# NCU_PCB_Rev2.net
KiCad netlist of a schematic drawn in EAGLE
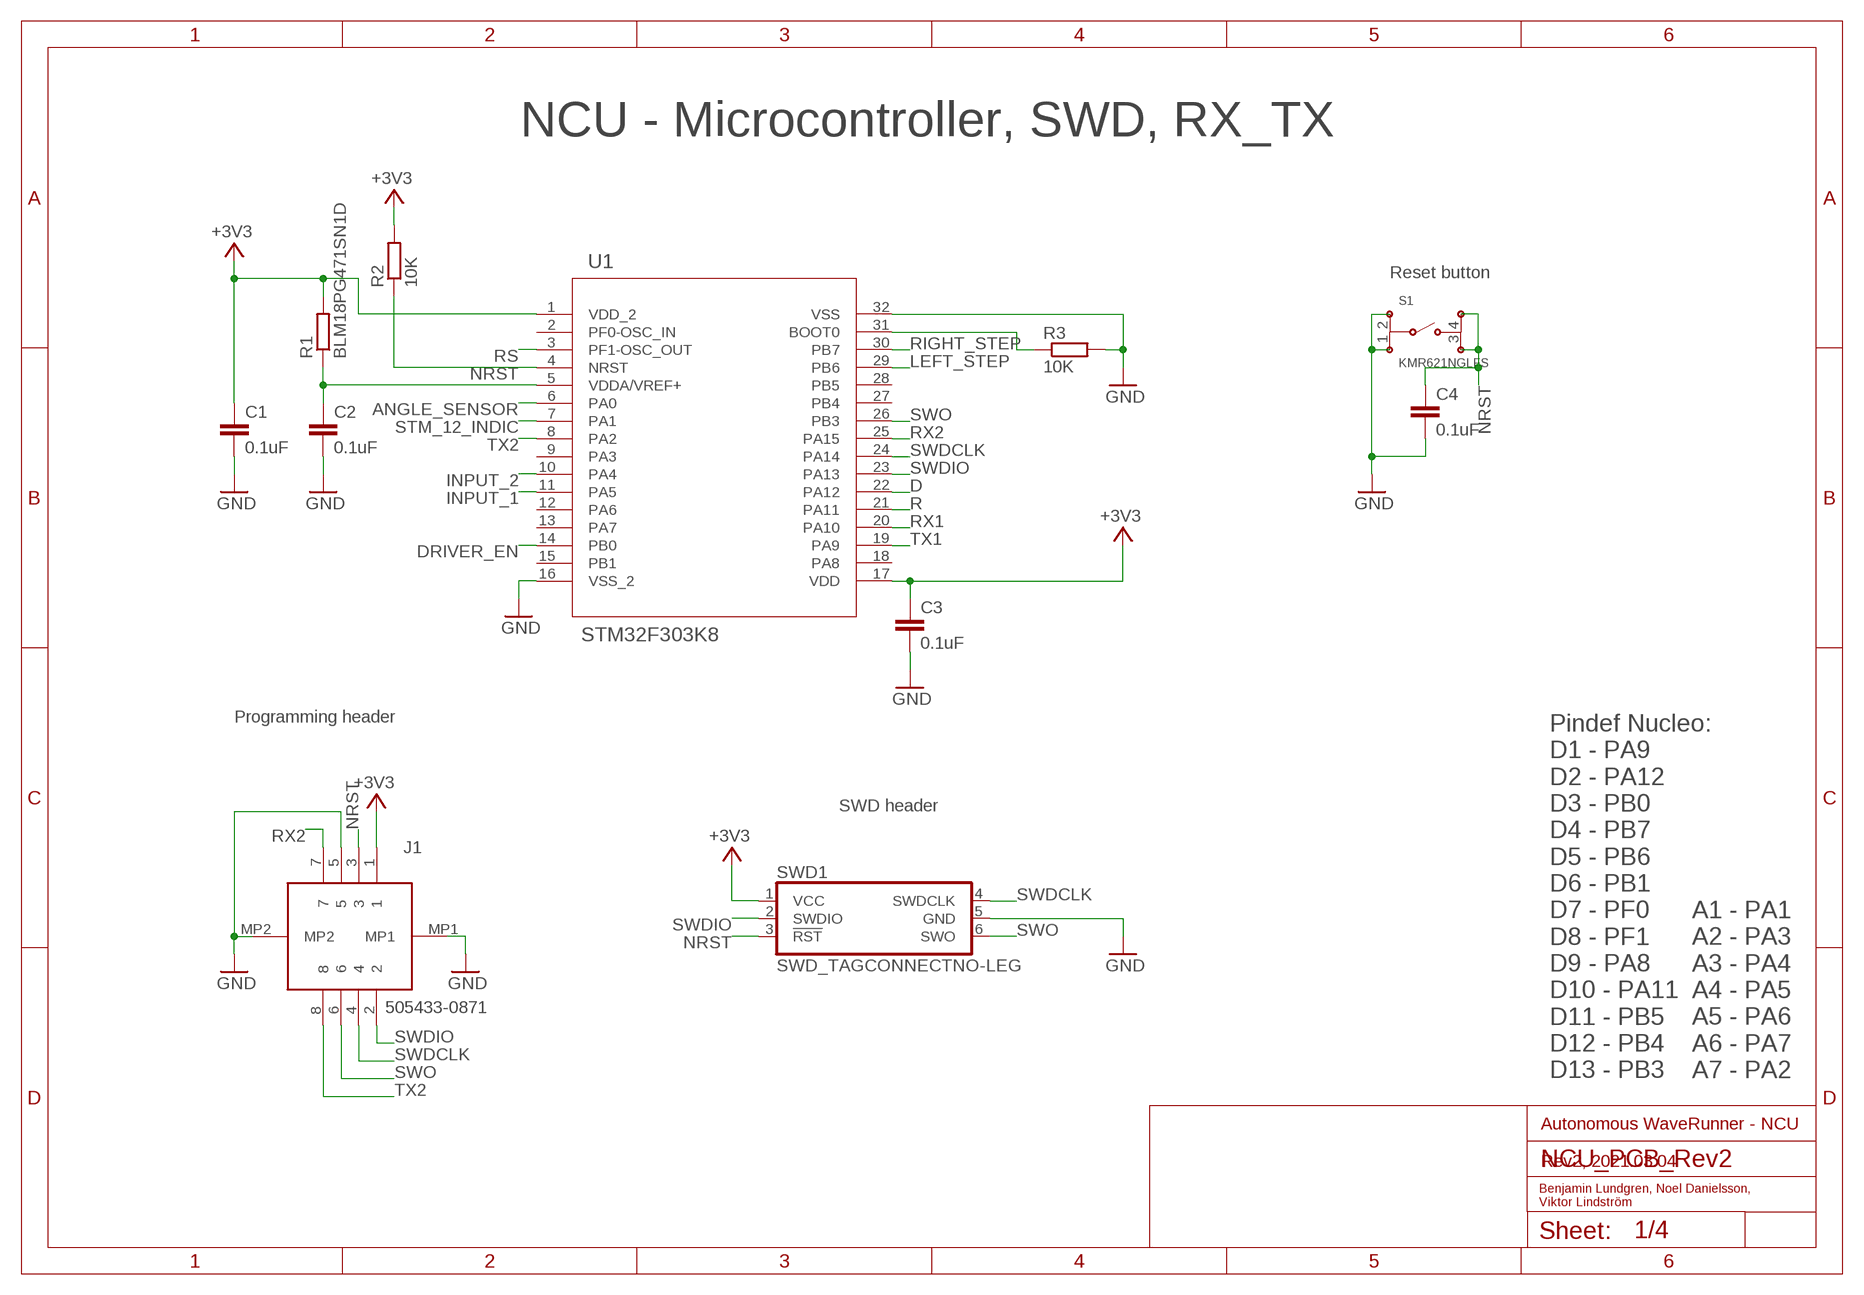
[diagram p0: schematic, sheet 1]
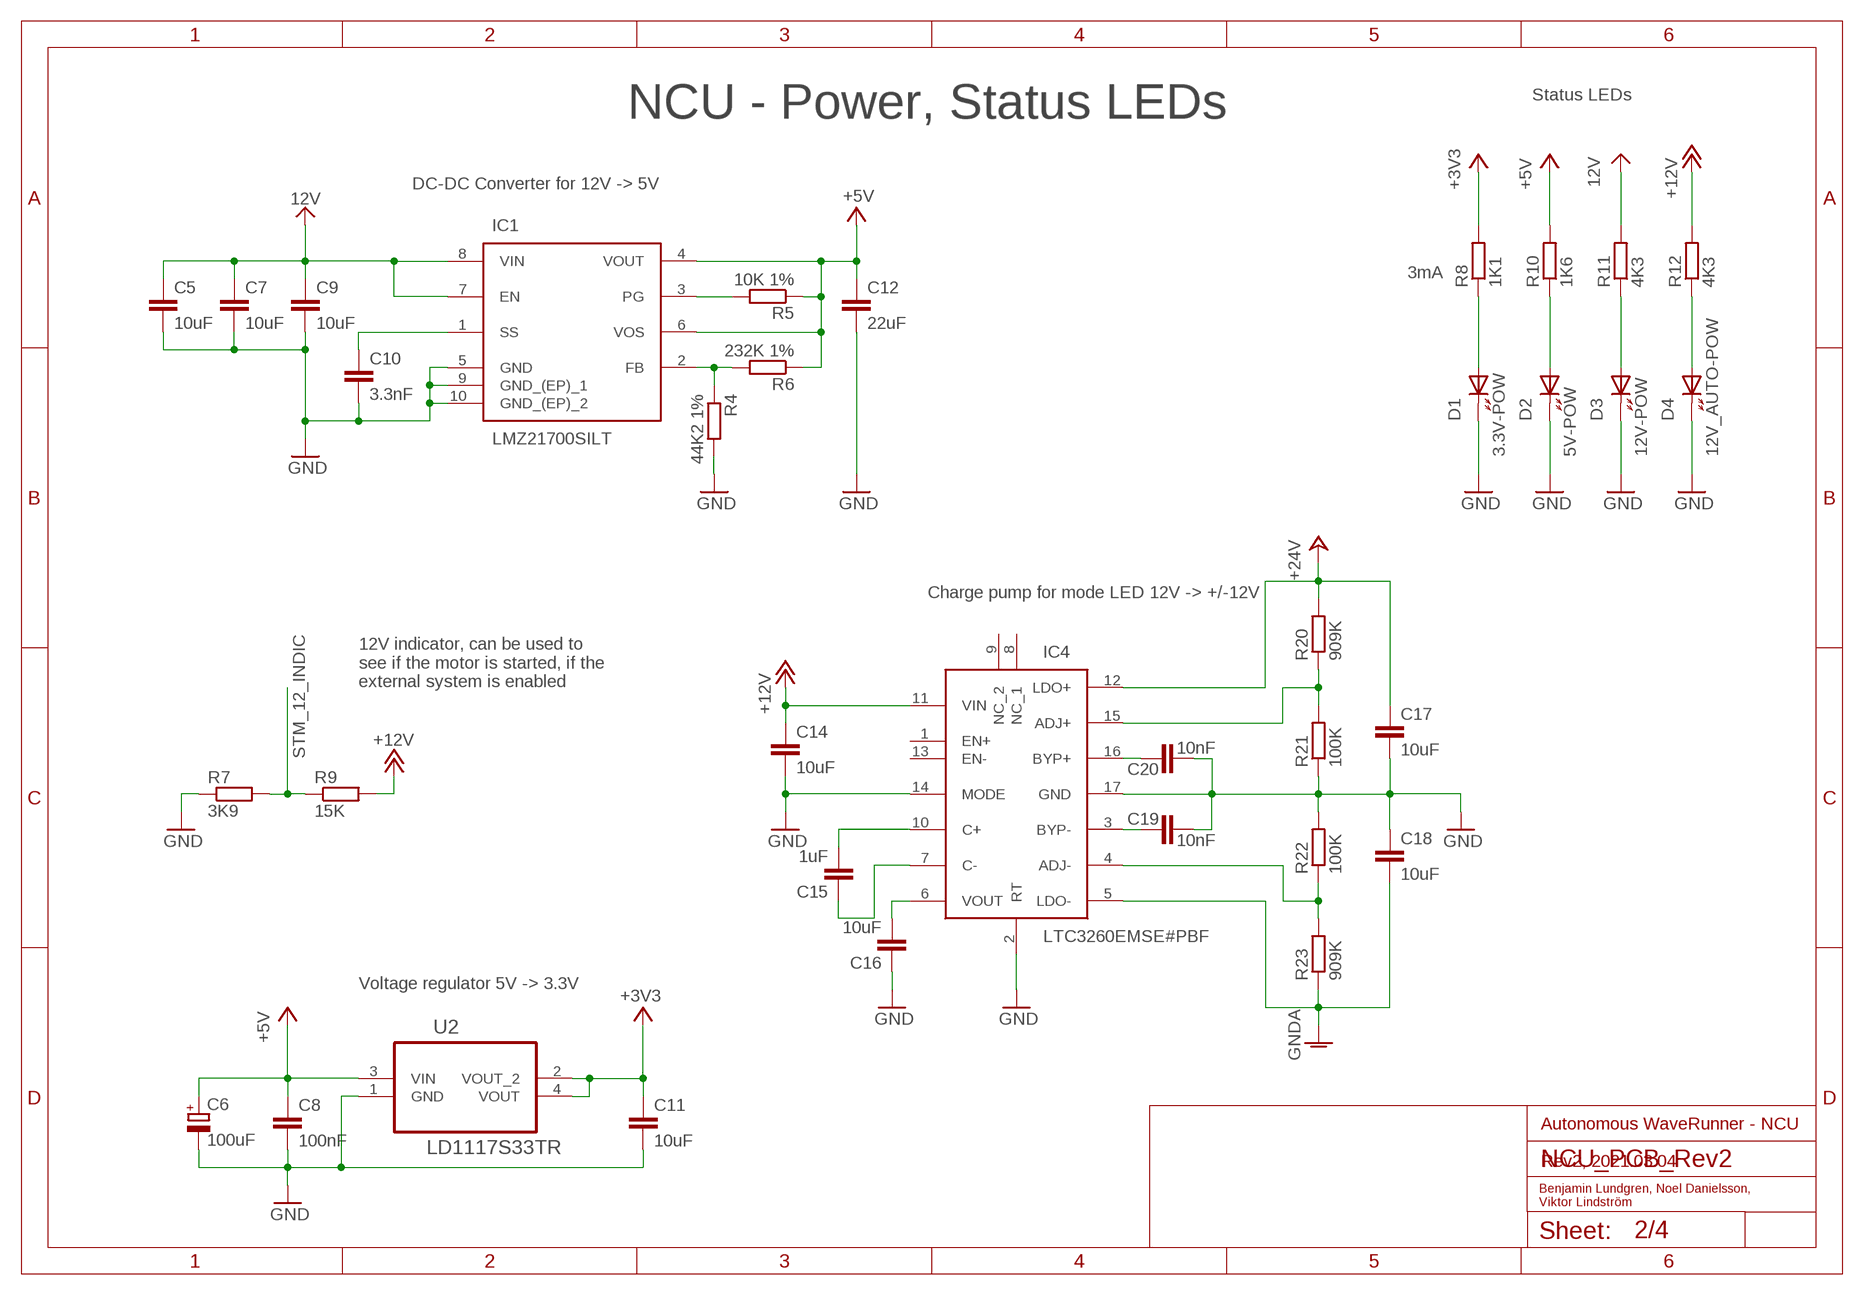
[diagram p1: schematic, sheet 2]
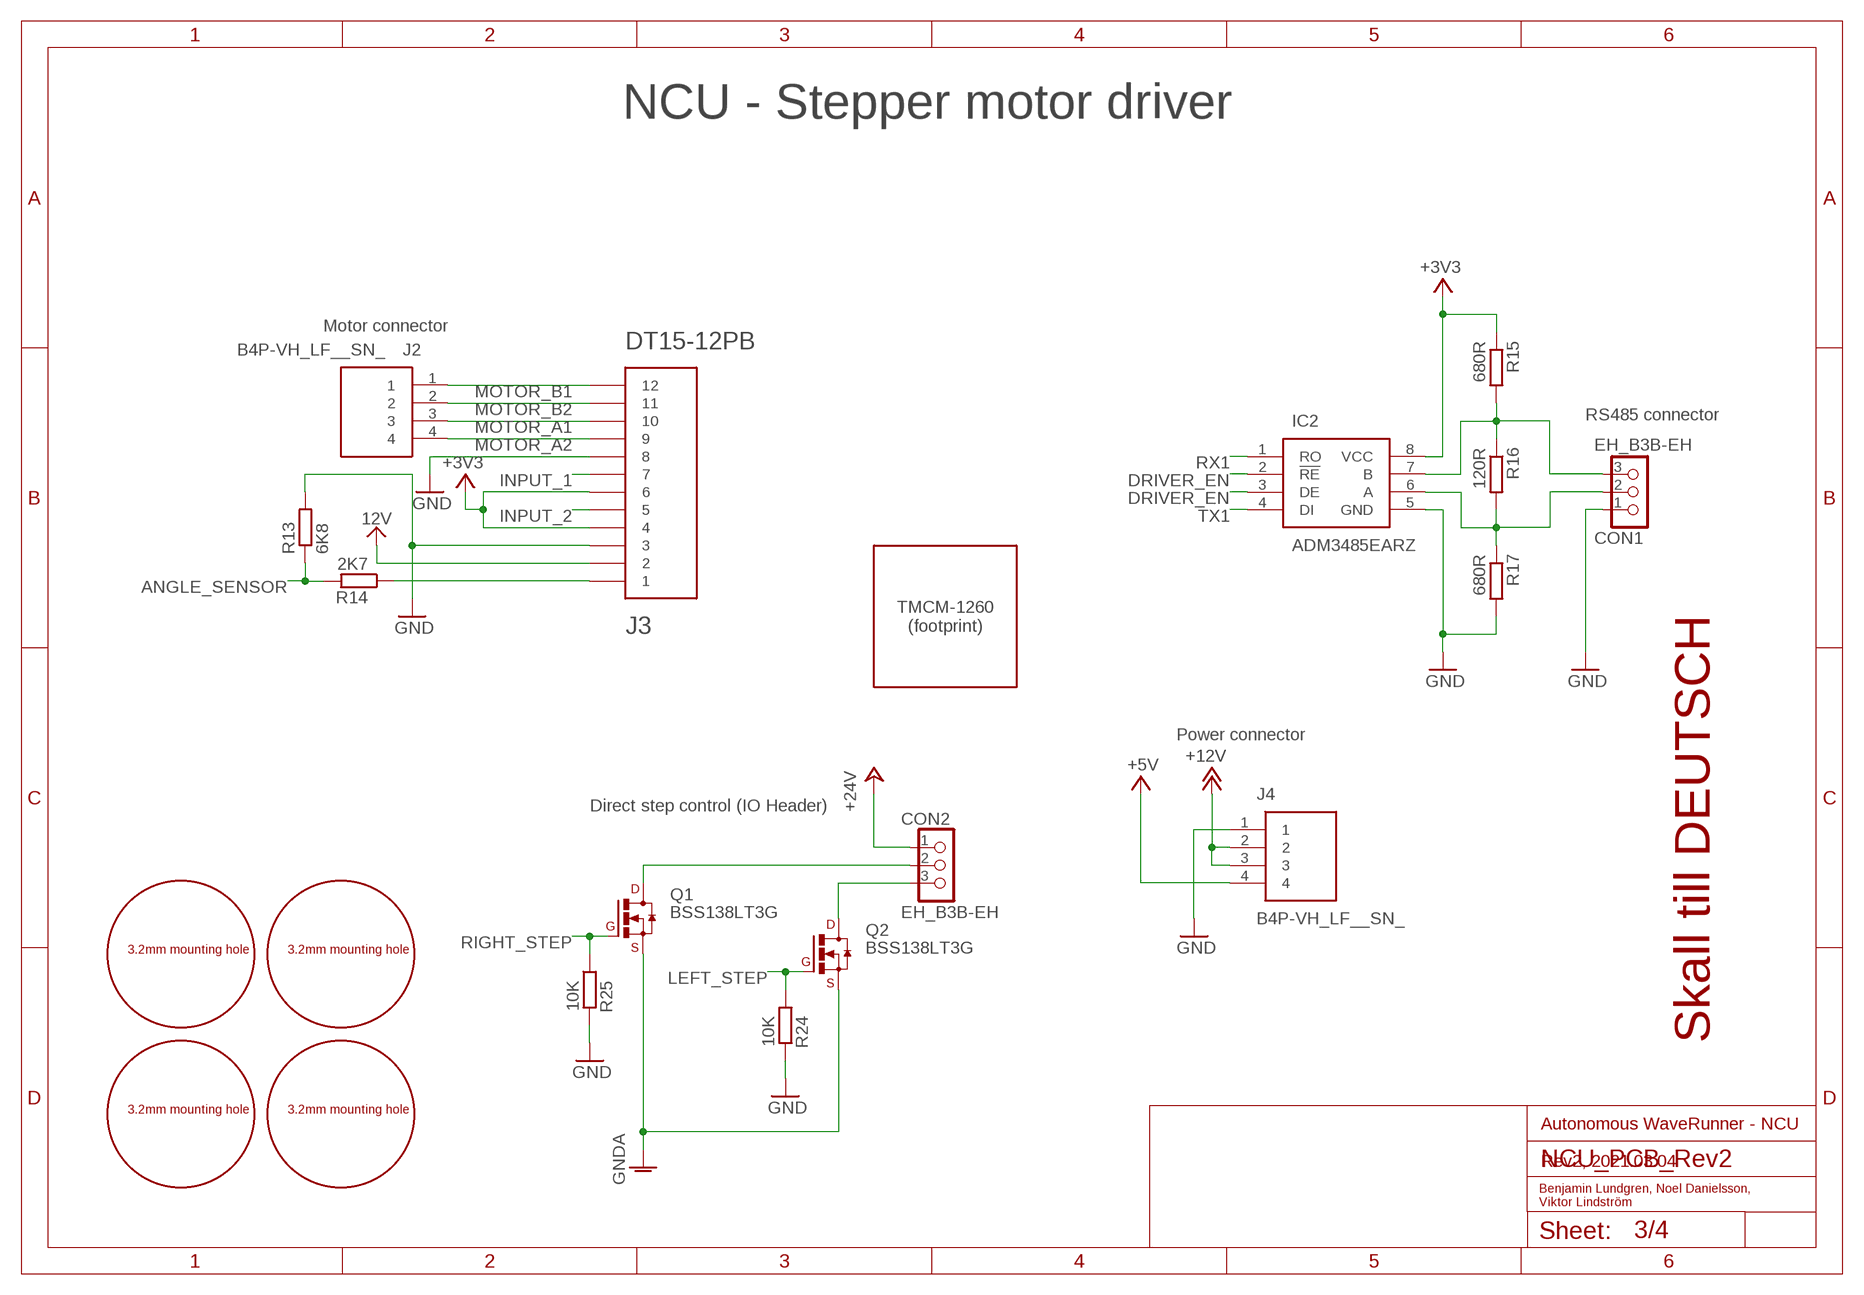
[diagram p2: schematic, sheet 3]
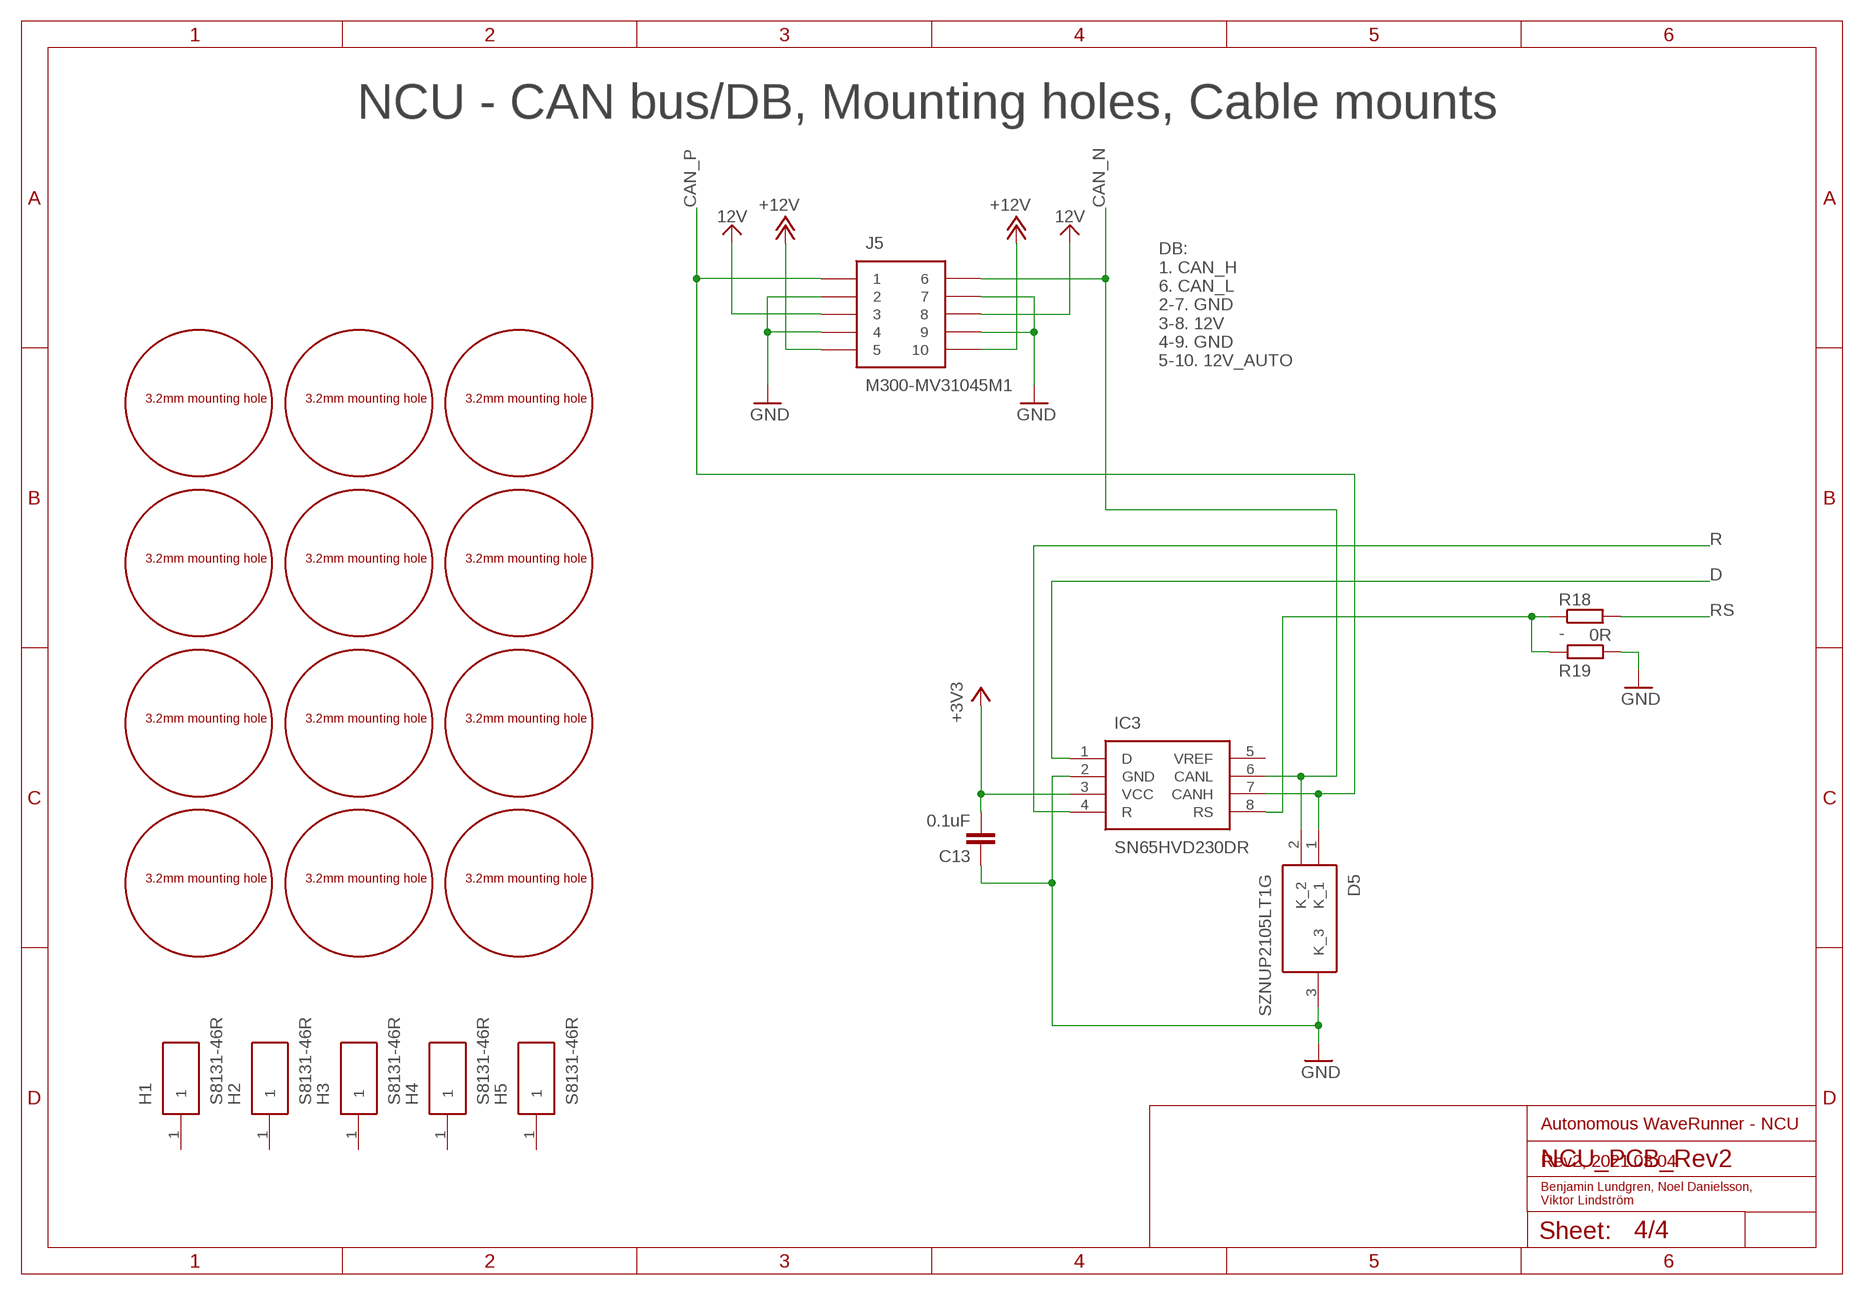
[diagram p3: schematic, sheet 4]

(export (version "E")
  (design (tool "Eeschema 10.0.6"))
  (components
    (comp (ref "C13")
      (value "0.1uF")
      (footprint "eagle-import:C0603")
      (libsource (lib "eagle-import") (part "C0603"))
    )
    (comp (ref "D5")
      (value "SZNUP2105LT1G")
      (footprint "eagle-import:SOT96P237X111-3N")
      (fields (field (name "MOUSER_PART_NUMBER") "863-SZNUP2105LT1G"))
      (libsource (lib "eagle-import") (part "SZNUP2105LT1G"))
    )
    (comp (ref "H1")
      (value "S8131-46R")
      (footprint "eagle-import:S813146R")
      (fields (field (name "RS_PART_NUMBER") "7884842P"))
      (libsource (lib "eagle-import") (part "S8131-46R"))
    )
    (comp (ref "H2")
      (value "S8131-46R")
      (footprint "eagle-import:S813146R")
      (fields (field (name "RS_PART_NUMBER") "7884842P"))
      (libsource (lib "eagle-import") (part "S8131-46R"))
    )
    (comp (ref "H3")
      (value "S8131-46R")
      (footprint "eagle-import:S813146R")
      (fields (field (name "RS_PART_NUMBER") "7884842P"))
      (libsource (lib "eagle-import") (part "S8131-46R"))
    )
    (comp (ref "H4")
      (value "S8131-46R")
      (footprint "eagle-import:S813146R")
      (fields (field (name "RS_PART_NUMBER") "7884842P"))
      (libsource (lib "eagle-import") (part "S8131-46R"))
    )
    (comp (ref "H5")
      (value "S8131-46R")
      (footprint "eagle-import:S813146R")
      (fields (field (name "RS_PART_NUMBER") "7884842P"))
      (libsource (lib "eagle-import") (part "S8131-46R"))
    )
    (comp (ref "HOLE5")
      (value "M3_MOUNTING_HOLE")
      (footprint "eagle-import:M3_MOUNTING_HOLE")
      (libsource (lib "eagle-import") (part "M3_MOUNTING_HOLE"))
    )
    (comp (ref "HOLE6")
      (value "M3_MOUNTING_HOLE")
      (footprint "eagle-import:M3_MOUNTING_HOLE")
      (libsource (lib "eagle-import") (part "M3_MOUNTING_HOLE"))
    )
    (comp (ref "HOLE7")
      (value "M3_MOUNTING_HOLE")
      (footprint "eagle-import:M3_MOUNTING_HOLE")
      (libsource (lib "eagle-import") (part "M3_MOUNTING_HOLE"))
    )
    (comp (ref "HOLE8")
      (value "M3_MOUNTING_HOLE")
      (footprint "eagle-import:M3_MOUNTING_HOLE")
      (libsource (lib "eagle-import") (part "M3_MOUNTING_HOLE"))
    )
    (comp (ref "HOLE9")
      (value "M3_MOUNTING_HOLE")
      (footprint "eagle-import:M3_MOUNTING_HOLE")
      (libsource (lib "eagle-import") (part "M3_MOUNTING_HOLE"))
    )
    (comp (ref "HOLE10")
      (value "M3_MOUNTING_HOLE")
      (footprint "eagle-import:M3_MOUNTING_HOLE")
      (libsource (lib "eagle-import") (part "M3_MOUNTING_HOLE"))
    )
    (comp (ref "HOLE11")
      (value "M3_MOUNTING_HOLE")
      (footprint "eagle-import:M3_MOUNTING_HOLE")
      (libsource (lib "eagle-import") (part "M3_MOUNTING_HOLE"))
    )
    (comp (ref "HOLE12")
      (value "M3_MOUNTING_HOLE")
      (footprint "eagle-import:M3_MOUNTING_HOLE")
      (libsource (lib "eagle-import") (part "M3_MOUNTING_HOLE"))
    )
    (comp (ref "HOLE13")
      (value "M3_MOUNTING_HOLE")
      (footprint "eagle-import:M3_MOUNTING_HOLE")
      (libsource (lib "eagle-import") (part "M3_MOUNTING_HOLE"))
    )
    (comp (ref "HOLE14")
      (value "M3_MOUNTING_HOLE")
      (footprint "eagle-import:M3_MOUNTING_HOLE")
      (libsource (lib "eagle-import") (part "M3_MOUNTING_HOLE"))
    )
    (comp (ref "HOLE15")
      (value "M3_MOUNTING_HOLE")
      (footprint "eagle-import:M3_MOUNTING_HOLE")
      (libsource (lib "eagle-import") (part "M3_MOUNTING_HOLE"))
    )
    (comp (ref "HOLE16")
      (value "M3_MOUNTING_HOLE")
      (footprint "eagle-import:M3_MOUNTING_HOLE")
      (libsource (lib "eagle-import") (part "M3_MOUNTING_HOLE"))
    )
    (comp (ref "IC3")
      (value "SN65HVD230DR")
      (footprint "eagle-import:SOT127P600X175-8N")
      (fields (field (name "MOUSER_PART_NUMBER") "595-SN65HVD230DR"))
      (libsource (lib "eagle-import") (part "SN65HVD230DR"))
    )
    (comp (ref "J5")
      (value "M300-MV31045M1")
      (footprint "eagle-import:M300MV31045M1")
      (libsource (lib "eagle-import") (part "M300-MV31045M1"))
    )
    (comp (ref "R18")
      (value "-")
      (footprint "eagle-import:R0603")
      (libsource (lib "eagle-import") (part "R0603"))
    )
    (comp (ref "R19")
      (value "0R")
      (footprint "eagle-import:R0603")
      (libsource (lib "eagle-import") (part "R0603"))
    )
    (comp (ref "CON1")
      (value "EH_B3B-EH")
      (footprint "eagle-import:B3B-EH")
      (libsource (lib "eagle-import") (part "EH_B3B-EH"))
    )
    (comp (ref "CON2")
      (value "EH_B3B-EH")
      (footprint "eagle-import:B3B-EH")
      (libsource (lib "eagle-import") (part "EH_B3B-EH"))
    )
    (comp (ref "HOLE1")
      (value "M3_MOUNTING_HOLE")
      (footprint "eagle-import:M3_MOUNTING_HOLE")
      (libsource (lib "eagle-import") (part "M3_MOUNTING_HOLE"))
    )
    (comp (ref "HOLE2")
      (value "M3_MOUNTING_HOLE")
      (footprint "eagle-import:M3_MOUNTING_HOLE")
      (libsource (lib "eagle-import") (part "M3_MOUNTING_HOLE"))
    )
    (comp (ref "HOLE3")
      (value "M3_MOUNTING_HOLE")
      (footprint "eagle-import:M3_MOUNTING_HOLE")
      (libsource (lib "eagle-import") (part "M3_MOUNTING_HOLE"))
    )
    (comp (ref "HOLE4")
      (value "M3_MOUNTING_HOLE")
      (footprint "eagle-import:M3_MOUNTING_HOLE")
      (libsource (lib "eagle-import") (part "M3_MOUNTING_HOLE"))
    )
    (comp (ref "IC2")
      (value "ADM3485EARZ")
      (footprint "eagle-import:SOIC127P600X175-8N")
      (fields (field (name "RS_PART_NUMBER") "0412709P"))
      (libsource (lib "eagle-import") (part "ADM3485EARZ"))
    )
    (comp (ref "J2")
      (value "B4P-VH_LF__SN_")
      (footprint "eagle-import:SHDR4W114P0X396_1X4_1578X850X9")
      (fields
        (field (name "MANUFACTURER_PART_NUMBER") "B4P-VH(LF)(SN)")
        (field (name "RS_PART_NUMBER") "8201157P")
      )
      (libsource (lib "eagle-import") (part "B4P-VH_LF__SN_"))
    )
    (comp (ref "J3")
      (value "DT15-12PB")
      (footprint "eagle-import:TE_DT15-12PB")
      (fields (field (name "MF") "TE Connectivity") (field (name "MPN") "DT15-12PB "))
      (libsource (lib "eagle-import") (part "DT15-12PB"))
    )
    (comp (ref "J4")
      (value "B4P-VH_LF__SN_")
      (footprint "eagle-import:SHDR4W114P0X396_1X4_1578X850X9")
      (fields
        (field (name "MANUFACTURER_PART_NUMBER") "B4P-VH(LF)(SN)")
        (field (name "RS_PART_NUMBER") "8201157P")
      )
      (libsource (lib "eagle-import") (part "B4P-VH_LF__SN_"))
    )
    (comp (ref "MOD1")
      (value "TMCM-1260")
      (footprint "eagle-import:TMCM_1260")
      (libsource (lib "eagle-import") (part "TMCM-1260"))
    )
    (comp (ref "Q1")
      (value "BSS138LT3G")
      (footprint "eagle-import:SOT23")
      (libsource (lib "eagle-import") (part "BSS138LT3G"))
    )
    (comp (ref "Q2")
      (value "BSS138LT3G")
      (footprint "eagle-import:SOT23")
      (libsource (lib "eagle-import") (part "BSS138LT3G"))
    )
    (comp (ref "R13")
      (value "6K8")
      (footprint "eagle-import:R0603")
      (libsource (lib "eagle-import") (part "R0603"))
    )
    (comp (ref "R14")
      (value "2K7")
      (footprint "eagle-import:R0603")
      (libsource (lib "eagle-import") (part "R0603"))
    )
    (comp (ref "R15")
      (value "680R")
      (footprint "eagle-import:R0603")
      (libsource (lib "eagle-import") (part "R0603"))
    )
    (comp (ref "R16")
      (value "120R")
      (footprint "eagle-import:R0603")
      (libsource (lib "eagle-import") (part "R0603"))
    )
    (comp (ref "R17")
      (value "680R")
      (footprint "eagle-import:R0603")
      (libsource (lib "eagle-import") (part "R0603"))
    )
    (comp (ref "R24")
      (value "10K")
      (footprint "eagle-import:R0603")
      (libsource (lib "eagle-import") (part "R0603"))
    )
    (comp (ref "R25")
      (value "10K")
      (footprint "eagle-import:R0603")
      (libsource (lib "eagle-import") (part "R0603"))
    )
    (comp (ref "C1")
      (value "0.1uF")
      (footprint "eagle-import:C0603")
      (libsource (lib "eagle-import") (part "C0603"))
    )
    (comp (ref "C2")
      (value "0.1uF")
      (footprint "eagle-import:C0603")
      (libsource (lib "eagle-import") (part "C0603"))
    )
    (comp (ref "C3")
      (value "0.1uF")
      (footprint "eagle-import:C0603")
      (libsource (lib "eagle-import") (part "C0603"))
    )
    (comp (ref "C4")
      (value "0.1uF")
      (footprint "eagle-import:C0603")
      (libsource (lib "eagle-import") (part "C0603"))
    )
    (comp (ref "J1")
      (value "505433-0871")
      (footprint "eagle-import:5054330871")
      (fields (field (name "MANUFACTURER_PART_NUMBER") "5054330871"))
      (libsource (lib "eagle-import") (part "505433-0871"))
    )
    (comp (ref "R1")
      (value "BLM18PG471SN1D")
      (footprint "eagle-import:R0603")
      (libsource (lib "eagle-import") (part "R0603"))
    )
    (comp (ref "R2")
      (value "10K")
      (footprint "eagle-import:R0603")
      (libsource (lib "eagle-import") (part "R0603"))
    )
    (comp (ref "R3")
      (value "10K")
      (footprint "eagle-import:R0603")
      (libsource (lib "eagle-import") (part "R0603"))
    )
    (comp (ref "S1")
      (value "KMR621NGLFS")
      (footprint "eagle-import:KMR621NGLFS")
      (libsource (lib "eagle-import") (part "KMR621NGLFS"))
    )
    (comp (ref "SWD1")
      (value "SWD_TAGCONNECTNO-LEG")
      (footprint "eagle-import:TC2030-IDC-NL")
      (libsource (lib "eagle-import") (part "SWD_TAGCONNECTNO-LEG"))
    )
    (comp (ref "U1")
      (value "STM32F303K8")
      (footprint "eagle-import:LQFP-32")
      (fields (field (name "MANUFACTURER_PART_NUMBER") "stm32f303_334kxt"))
      (libsource (lib "eagle-import") (part "STM32F303K8"))
    )
    (comp (ref "C5")
      (value "10uF")
      (footprint "eagle-import:C1206")
      (libsource (lib "eagle-import") (part "C1206"))
    )
    (comp (ref "C6")
      (value "100uF")
      (footprint "eagle-import:PANASONIC_C")
      (libsource (lib "eagle-import") (part "PANASONIC_C"))
    )
    (comp (ref "C7")
      (value "10uF")
      (footprint "eagle-import:C1206")
      (libsource (lib "eagle-import") (part "C1206"))
    )
    (comp (ref "C8")
      (value "100nF")
      (footprint "eagle-import:C0603")
      (libsource (lib "eagle-import") (part "C0603"))
    )
    (comp (ref "C9")
      (value "10uF")
      (footprint "eagle-import:C1206")
      (libsource (lib "eagle-import") (part "C1206"))
    )
    (comp (ref "C10")
      (value "3.3nF")
      (footprint "eagle-import:C0603")
      (libsource (lib "eagle-import") (part "C0603"))
    )
    (comp (ref "C11")
      (value "10uF")
      (footprint "eagle-import:C0805")
      (libsource (lib "eagle-import") (part "C0805"))
    )
    (comp (ref "C12")
      (value "22uF")
      (footprint "eagle-import:C0805")
      (libsource (lib "eagle-import") (part "C0805"))
    )
    (comp (ref "C14")
      (value "10uF")
      (footprint "eagle-import:C1206")
      (libsource (lib "eagle-import") (part "C1206"))
    )
    (comp (ref "C15")
      (value "1uF")
      (footprint "eagle-import:C0805")
      (libsource (lib "eagle-import") (part "C0805"))
    )
    (comp (ref "C16")
      (value "10uF")
      (footprint "eagle-import:C1206")
      (libsource (lib "eagle-import") (part "C1206"))
    )
    (comp (ref "C17")
      (value "10uF")
      (footprint "eagle-import:C1206")
      (libsource (lib "eagle-import") (part "C1206"))
    )
    (comp (ref "C18")
      (value "10uF")
      (footprint "eagle-import:C1206")
      (libsource (lib "eagle-import") (part "C1206"))
    )
    (comp (ref "C19")
      (value "10nF")
      (footprint "eagle-import:C0603")
      (libsource (lib "eagle-import") (part "C0603"))
    )
    (comp (ref "C20")
      (value "10nF")
      (footprint "eagle-import:C0603")
      (libsource (lib "eagle-import") (part "C0603"))
    )
    (comp (ref "D1")
      (value "3.3V-POW")
      (footprint "eagle-import:CHIP-LED0805")
      (libsource (lib "eagle-import") (part "CHIP-LED0805"))
    )
    (comp (ref "D2")
      (value "5V-POW")
      (footprint "eagle-import:CHIP-LED0805")
      (libsource (lib "eagle-import") (part "CHIP-LED0805"))
    )
    (comp (ref "D3")
      (value "12V-POW")
      (footprint "eagle-import:CHIP-LED0805")
      (libsource (lib "eagle-import") (part "CHIP-LED0805"))
    )
    (comp (ref "D4")
      (value "12V_AUTO-POW")
      (footprint "eagle-import:CHIP-LED0805")
      (libsource (lib "eagle-import") (part "CHIP-LED0805"))
    )
    (comp (ref "IC1")
      (value "LMZ21700SILT")
      (footprint "eagle-import:SIL0008E")
      (fields (field (name "RS_PART_NUMBER") "9009750P"))
      (libsource (lib "eagle-import") (part "LMZ21700SILT"))
    )
    (comp (ref "IC4")
      (value "LTC3260EMSE#PBF")
      (footprint "eagle-import:SOP50P490X110-17N")
      (fields (field (name "RS_PART_NUMBER") "8516768P"))
      (libsource (lib "eagle-import") (part "LTC3260EMSE#PBF"))
    )
    (comp (ref "R4")
      (value "44K2 1%")
      (footprint "eagle-import:R0603")
      (libsource (lib "eagle-import") (part "R0603"))
    )
    (comp (ref "R5")
      (value "10K 1%")
      (footprint "eagle-import:R0603")
      (libsource (lib "eagle-import") (part "R0603"))
    )
    (comp (ref "R6")
      (value "232K 1%")
      (footprint "eagle-import:R0603")
      (libsource (lib "eagle-import") (part "R0603"))
    )
    (comp (ref "R7")
      (value "3K9")
      (footprint "eagle-import:R0603")
      (libsource (lib "eagle-import") (part "R0603"))
    )
    (comp (ref "R8")
      (value "1K1")
      (footprint "eagle-import:R0603")
      (libsource (lib "eagle-import") (part "R0603"))
    )
    (comp (ref "R9")
      (value "15K")
      (footprint "eagle-import:R0603")
      (libsource (lib "eagle-import") (part "R0603"))
    )
    (comp (ref "R10")
      (value "1K6")
      (footprint "eagle-import:R0603")
      (libsource (lib "eagle-import") (part "R0603"))
    )
    (comp (ref "R11")
      (value "4K3")
      (footprint "eagle-import:R0603")
      (libsource (lib "eagle-import") (part "R0603"))
    )
    (comp (ref "R12")
      (value "4K3")
      (footprint "eagle-import:R0603")
      (libsource (lib "eagle-import") (part "R0603"))
    )
    (comp (ref "R20")
      (value "909K")
      (footprint "eagle-import:R0603")
      (libsource (lib "eagle-import") (part "R0603"))
    )
    (comp (ref "R21")
      (value "100K")
      (footprint "eagle-import:R0603")
      (libsource (lib "eagle-import") (part "R0603"))
    )
    (comp (ref "R22")
      (value "100K")
      (footprint "eagle-import:R0603")
      (libsource (lib "eagle-import") (part "R0603"))
    )
    (comp (ref "R23")
      (value "909K")
      (footprint "eagle-import:R0603")
      (libsource (lib "eagle-import") (part "R0603"))
    )
    (comp (ref "U2")
      (value "LD1117S33TR")
      (footprint "eagle-import:SOT230P700X180-4N")
      (libsource (lib "eagle-import") (part "LD1117S33TR"))
    )
  )
  (nets
    (net (code "1") (name "+3V3") (class "Default")
      (node (ref "C1") (pin "1") (pinfunction "1_1") (pintype "passive"))
      (node (ref "C11") (pin "1") (pinfunction "1_1") (pintype "passive"))
      (node (ref "C13") (pin "2") (pinfunction "2_2") (pintype "passive"))
      (node (ref "C3") (pin "1") (pinfunction "1_1") (pintype "passive"))
      (node (ref "IC2") (pin "8") (pinfunction "VCC_8") (pintype "bidirectional"))
      (node (ref "IC3") (pin "3") (pinfunction "VCC_3") (pintype "bidirectional"))
      (node (ref "J1") (pin "1") (pinfunction "1_1") (pintype "bidirectional"))
      (node (ref "J3") (pin "4") (pinfunction "4_4") (pintype "passive"))
      (node (ref "J3") (pin "6") (pinfunction "6_6") (pintype "passive"))
      (node (ref "R1") (pin "2") (pinfunction "2_2") (pintype "passive"))
      (node (ref "R15") (pin "1") (pinfunction "1_1") (pintype "passive"))
      (node (ref "R2") (pin "2") (pinfunction "2_2") (pintype "passive"))
      (node (ref "R8") (pin "2") (pinfunction "2_2") (pintype "passive"))
      (node (ref "SWD1") (pin "1") (pinfunction "VCC_1") (pintype "passive"))
      (node (ref "U1") (pin "1") (pinfunction "VDD_2_1") (pintype "power_in"))
      (node (ref "U1") (pin "17") (pinfunction "VDD_17") (pintype "power_in"))
      (node (ref "U2") (pin "2") (pinfunction "VOUT_2_2") (pintype "output"))
      (node (ref "U2") (pin "4") (pinfunction "VOUT_4") (pintype "output"))
    )
    (net (code "2") (name "+5V") (class "Default")
      (node (ref "C12") (pin "1") (pinfunction "1_1") (pintype "passive"))
      (node (ref "C6") (pin "+") (pinfunction "+_+") (pintype "passive"))
      (node (ref "C8") (pin "1") (pinfunction "1_1") (pintype "passive"))
      (node (ref "IC1") (pin "4") (pinfunction "VOUT_4") (pintype "output"))
      (node (ref "IC1") (pin "6") (pinfunction "VOS_6") (pintype "bidirectional"))
      (node (ref "J4") (pin "4") (pinfunction "4_4") (pintype "bidirectional"))
      (node (ref "R10") (pin "2") (pinfunction "2_2") (pintype "passive"))
      (node (ref "R5") (pin "1") (pinfunction "1_1") (pintype "passive"))
      (node (ref "R6") (pin "1") (pinfunction "1_1") (pintype "passive"))
      (node (ref "U2") (pin "3") (pinfunction "VIN_3") (pintype "input"))
    )
    (net (code "3") (name "+12V") (class "Default")
      (node (ref "C14") (pin "1") (pinfunction "1_1") (pintype "passive"))
      (node (ref "IC4") (pin "11") (pinfunction "VIN_11") (pintype "power_in"))
      (node (ref "J4") (pin "2") (pinfunction "2_2") (pintype "bidirectional"))
      (node (ref "J4") (pin "3") (pinfunction "3_3") (pintype "bidirectional"))
      (node (ref "J5") (pin "10") (pinfunction "10_10") (pintype "bidirectional"))
      (node (ref "J5") (pin "5") (pinfunction "5_5") (pintype "bidirectional"))
      (node (ref "R12") (pin "2") (pinfunction "2_2") (pintype "passive"))
      (node (ref "R9") (pin "2") (pinfunction "2_2") (pintype "passive"))
    )
    (net (code "4") (name "+24V") (class "Default")
      (node (ref "C17") (pin "1") (pinfunction "1_1") (pintype "passive"))
      (node (ref "CON2") (pin "1") (pinfunction "1_1") (pintype "passive"))
      (node (ref "IC4") (pin "12") (pinfunction "LDO+_12") (pintype "output"))
      (node (ref "R20") (pin "2") (pinfunction "2_2") (pintype "passive"))
    )
    (net (code "5") (name "12V") (class "Default")
      (node (ref "C5") (pin "1") (pinfunction "1_1") (pintype "passive"))
      (node (ref "C7") (pin "1") (pinfunction "1_1") (pintype "passive"))
      (node (ref "C9") (pin "1") (pinfunction "1_1") (pintype "passive"))
      (node (ref "IC1") (pin "7") (pinfunction "EN_7") (pintype "bidirectional"))
      (node (ref "IC1") (pin "8") (pinfunction "VIN_8") (pintype "input"))
      (node (ref "J3") (pin "2") (pinfunction "2_2") (pintype "passive"))
      (node (ref "J5") (pin "3") (pinfunction "3_3") (pintype "bidirectional"))
      (node (ref "J5") (pin "8") (pinfunction "8_8") (pintype "bidirectional"))
      (node (ref "R11") (pin "2") (pinfunction "2_2") (pintype "passive"))
    )
    (net (code "6") (name "ANGLE_SENSOR") (class "Default")
      (node (ref "R13") (pin "1") (pinfunction "1_1") (pintype "passive"))
      (node (ref "R14") (pin "2") (pinfunction "2_2") (pintype "passive"))
      (node (ref "U1") (pin "6") (pinfunction "PA0_6") (pintype "bidirectional"))
    )
    (net (code "7") (name "CAN_N") (class "Default")
      (node (ref "D5") (pin "2") (pinfunction "K_2_2") (pintype "bidirectional"))
      (node (ref "IC3") (pin "6") (pinfunction "CANL_6") (pintype "bidirectional"))
      (node (ref "J5") (pin "6") (pinfunction "6_6") (pintype "bidirectional"))
    )
    (net (code "8") (name "CAN_P") (class "Default")
      (node (ref "D5") (pin "1") (pinfunction "K_1_1") (pintype "bidirectional"))
      (node (ref "IC3") (pin "7") (pinfunction "CANH_7") (pintype "bidirectional"))
      (node (ref "J5") (pin "1") (pinfunction "1_1") (pintype "bidirectional"))
    )
    (net (code "9") (name "D") (class "Default")
      (node (ref "IC3") (pin "1") (pinfunction "D_1") (pintype "bidirectional"))
      (node (ref "U1") (pin "22") (pinfunction "PA12_22") (pintype "bidirectional"))
    )
    (net (code "10") (name "DRIVER_EN") (class "Default")
      (node (ref "IC2") (pin "2") (pinfunction "~{RE}_2") (pintype "bidirectional"))
      (node (ref "IC2") (pin "3") (pinfunction "DE_3") (pintype "bidirectional"))
      (node (ref "U1") (pin "14") (pinfunction "PB0_14") (pintype "bidirectional"))
    )
    (net (code "11") (name "GND") (class "Default")
      (node (ref "C1") (pin "2") (pinfunction "2_2") (pintype "passive"))
      (node (ref "C10") (pin "2") (pinfunction "2_2") (pintype "passive"))
      (node (ref "C11") (pin "2") (pinfunction "2_2") (pintype "passive"))
      (node (ref "C12") (pin "2") (pinfunction "2_2") (pintype "passive"))
      (node (ref "C13") (pin "1") (pinfunction "1_1") (pintype "passive"))
      (node (ref "C14") (pin "2") (pinfunction "2_2") (pintype "passive"))
      (node (ref "C16") (pin "1") (pinfunction "1_1") (pintype "passive"))
      (node (ref "C17") (pin "2") (pinfunction "2_2") (pintype "passive"))
      (node (ref "C18") (pin "1") (pinfunction "1_1") (pintype "passive"))
      (node (ref "C19") (pin "2") (pinfunction "2_2") (pintype "passive"))
      (node (ref "C2") (pin "2") (pinfunction "2_2") (pintype "passive"))
      (node (ref "C20") (pin "2") (pinfunction "2_2") (pintype "passive"))
      (node (ref "C3") (pin "2") (pinfunction "2_2") (pintype "passive"))
      (node (ref "C4") (pin "2") (pinfunction "2_2") (pintype "passive"))
      (node (ref "C5") (pin "2") (pinfunction "2_2") (pintype "passive"))
      (node (ref "C6") (pin "-") (pinfunction "-_-") (pintype "passive"))
      (node (ref "C7") (pin "2") (pinfunction "2_2") (pintype "passive"))
      (node (ref "C8") (pin "2") (pinfunction "2_2") (pintype "passive"))
      (node (ref "C9") (pin "2") (pinfunction "2_2") (pintype "passive"))
      (node (ref "CON1") (pin "1") (pinfunction "1_1") (pintype "passive"))
      (node (ref "D1") (pin "C") (pinfunction "K_C") (pintype "passive"))
      (node (ref "D2") (pin "C") (pinfunction "K_C") (pintype "passive"))
      (node (ref "D3") (pin "C") (pinfunction "K_C") (pintype "passive"))
      (node (ref "D4") (pin "C") (pinfunction "K_C") (pintype "passive"))
      (node (ref "D5") (pin "3") (pinfunction "K_3_3") (pintype "bidirectional"))
      (node (ref "IC1") (pin "10") (pinfunction "GND_(EP)_2_10") (pintype "power_in"))
      (node (ref "IC1") (pin "5") (pinfunction "GND_5") (pintype "power_in"))
      (node (ref "IC1") (pin "9") (pinfunction "GND_(EP)_1_9") (pintype "power_in"))
      (node (ref "IC2") (pin "5") (pinfunction "GND_5") (pintype "bidirectional"))
      (node (ref "IC3") (pin "2") (pinfunction "GND_2") (pintype "bidirectional"))
      (node (ref "IC4") (pin "14") (pinfunction "MODE_14") (pintype "input"))
      (node (ref "IC4") (pin "17") (pinfunction "GND_17") (pintype "power_in"))
      (node (ref "IC4") (pin "2") (pinfunction "RT_2") (pintype "input"))
      (node (ref "J1") (pin "5") (pinfunction "5_5") (pintype "bidirectional"))
      (node (ref "J1") (pin "MP1") (pinfunction "MP1_MP1") (pintype "bidirectional"))
      (node (ref "J1") (pin "MP2") (pinfunction "MP2_MP2") (pintype "bidirectional"))
      (node (ref "J3") (pin "3") (pinfunction "3_3") (pintype "passive"))
      (node (ref "J3") (pin "8") (pinfunction "8_8") (pintype "passive"))
      (node (ref "J4") (pin "1") (pinfunction "1_1") (pintype "bidirectional"))
      (node (ref "J5") (pin "2") (pinfunction "2_2") (pintype "bidirectional"))
      (node (ref "J5") (pin "4") (pinfunction "4_4") (pintype "bidirectional"))
      (node (ref "J5") (pin "7") (pinfunction "7_7") (pintype "bidirectional"))
      (node (ref "J5") (pin "9") (pinfunction "9_9") (pintype "bidirectional"))
      (node (ref "R13") (pin "2") (pinfunction "2_2") (pintype "passive"))
      (node (ref "R17") (pin "2") (pinfunction "2_2") (pintype "passive"))
      (node (ref "R19") (pin "1") (pinfunction "1_1") (pintype "passive"))
      (node (ref "R21") (pin "1") (pinfunction "1_1") (pintype "passive"))
      (node (ref "R22") (pin "2") (pinfunction "2_2") (pintype "passive"))
      (node (ref "R24") (pin "2") (pinfunction "2_2") (pintype "passive"))
      (node (ref "R25") (pin "2") (pinfunction "2_2") (pintype "passive"))
      (node (ref "R3") (pin "2") (pinfunction "2_2") (pintype "passive"))
      (node (ref "R4") (pin "2") (pinfunction "2_2") (pintype "passive"))
      (node (ref "R7") (pin "1") (pinfunction "1_1") (pintype "passive"))
      (node (ref "S1") (pin "1") (pinfunction "1_1") (pintype "bidirectional"))
      (node (ref "S1") (pin "2") (pinfunction "2_2") (pintype "bidirectional"))
      (node (ref "SWD1") (pin "5") (pinfunction "GND_5") (pintype "passive"))
      (node (ref "U1") (pin "16") (pinfunction "VSS_2_16") (pintype "power_in"))
      (node (ref "U1") (pin "32") (pinfunction "VSS_32") (pintype "power_in"))
      (node (ref "U2") (pin "1") (pinfunction "GND_1") (pintype "passive"))
    )
    (net (code "12") (name "GNDA") (class "Default")
      (node (ref "C18") (pin "2") (pinfunction "2_2") (pintype "passive"))
      (node (ref "IC4") (pin "5") (pinfunction "LDO-_5") (pintype "output"))
      (node (ref "Q1") (pin "2") (pinfunction "S_2") (pintype "passive"))
      (node (ref "Q2") (pin "2") (pinfunction "S_2") (pintype "passive"))
      (node (ref "R23") (pin "1") (pinfunction "1_1") (pintype "passive"))
    )
    (net (code "13") (name "INPUT_1") (class "Default")
      (node (ref "J3") (pin "7") (pinfunction "7_7") (pintype "passive"))
      (node (ref "U1") (pin "11") (pinfunction "PA5_11") (pintype "bidirectional"))
    )
    (net (code "14") (name "INPUT_2") (class "Default")
      (node (ref "J3") (pin "5") (pinfunction "5_5") (pintype "passive"))
      (node (ref "U1") (pin "10") (pinfunction "PA4_10") (pintype "bidirectional"))
    )
    (net (code "15") (name "LEFT_STEP") (class "Default")
      (node (ref "Q2") (pin "1") (pinfunction "G_1") (pintype "passive"))
      (node (ref "R24") (pin "1") (pinfunction "1_1") (pintype "passive"))
      (node (ref "U1") (pin "29") (pinfunction "PB6_29") (pintype "bidirectional"))
    )
    (net (code "16") (name "MOTOR_A1") (class "Default")
      (node (ref "J2") (pin "3") (pinfunction "3_3") (pintype "bidirectional"))
      (node (ref "J3") (pin "10") (pinfunction "10_10") (pintype "passive"))
    )
    (net (code "17") (name "MOTOR_A2") (class "Default")
      (node (ref "J2") (pin "4") (pinfunction "4_4") (pintype "bidirectional"))
      (node (ref "J3") (pin "9") (pinfunction "9_9") (pintype "passive"))
    )
    (net (code "18") (name "MOTOR_B1") (class "Default")
      (node (ref "J2") (pin "1") (pinfunction "1_1") (pintype "bidirectional"))
      (node (ref "J3") (pin "12") (pinfunction "12_12") (pintype "passive"))
    )
    (net (code "19") (name "MOTOR_B2") (class "Default")
      (node (ref "J2") (pin "2") (pinfunction "2_2") (pintype "bidirectional"))
      (node (ref "J3") (pin "11") (pinfunction "11_11") (pintype "passive"))
    )
    (net (code "20") (name "NRST") (class "Default")
      (node (ref "C4") (pin "1") (pinfunction "1_1") (pintype "passive"))
      (node (ref "J1") (pin "3") (pinfunction "3_3") (pintype "bidirectional"))
      (node (ref "R2") (pin "1") (pinfunction "1_1") (pintype "passive"))
      (node (ref "S1") (pin "3") (pinfunction "3_3") (pintype "bidirectional"))
      (node (ref "S1") (pin "4") (pinfunction "4_4") (pintype "bidirectional"))
      (node (ref "SWD1") (pin "3") (pinfunction "~{RST}_3") (pintype "passive"))
      (node (ref "U1") (pin "4") (pinfunction "NRST_4") (pintype "bidirectional"))
    )
    (net (code "21") (name "Net-(D1-PadA)") (class "Default")
      (node (ref "D1") (pin "A") (pinfunction "A_A") (pintype "passive"))
      (node (ref "R8") (pin "1") (pinfunction "1_1") (pintype "passive"))
    )
    (net (code "22") (name "Net-(D2-PadA)") (class "Default")
      (node (ref "D2") (pin "A") (pinfunction "A_A") (pintype "passive"))
      (node (ref "R10") (pin "1") (pinfunction "1_1") (pintype "passive"))
    )
    (net (code "23") (name "Net-(D3-PadA)") (class "Default")
      (node (ref "D3") (pin "A") (pinfunction "A_A") (pintype "passive"))
      (node (ref "R11") (pin "1") (pinfunction "1_1") (pintype "passive"))
    )
    (net (code "24") (name "Net-(D4-PadA)") (class "Default")
      (node (ref "D4") (pin "A") (pinfunction "A_A") (pintype "passive"))
      (node (ref "R12") (pin "1") (pinfunction "1_1") (pintype "passive"))
    )
    (net (code "25") (name "Net-(IC1-FB)") (class "Default")
      (node (ref "IC1") (pin "2") (pinfunction "FB_2") (pintype "bidirectional"))
      (node (ref "R4") (pin "1") (pinfunction "1_1") (pintype "passive"))
      (node (ref "R6") (pin "2") (pinfunction "2_2") (pintype "passive"))
    )
    (net (code "26") (name "Net-(IC1-PG)") (class "Default")
      (node (ref "IC1") (pin "3") (pinfunction "PG_3") (pintype "bidirectional"))
      (node (ref "R5") (pin "2") (pinfunction "2_2") (pintype "passive"))
    )
    (net (code "27") (name "Net-(IC1-SS)") (class "Default")
      (node (ref "C10") (pin "1") (pinfunction "1_1") (pintype "passive"))
      (node (ref "IC1") (pin "1") (pinfunction "SS_1") (pintype "bidirectional"))
    )
    (net (code "28") (name "Net-(IC2-A)") (class "Default")
      (node (ref "CON1") (pin "2") (pinfunction "2_2") (pintype "passive"))
      (node (ref "IC2") (pin "6") (pinfunction "A_6") (pintype "bidirectional"))
      (node (ref "R16") (pin "2") (pinfunction "2_2") (pintype "passive"))
      (node (ref "R17") (pin "1") (pinfunction "1_1") (pintype "passive"))
    )
    (net (code "29") (name "Net-(IC2-B)") (class "Default")
      (node (ref "CON1") (pin "3") (pinfunction "3_3") (pintype "passive"))
      (node (ref "IC2") (pin "7") (pinfunction "B_7") (pintype "bidirectional"))
      (node (ref "R15") (pin "2") (pinfunction "2_2") (pintype "passive"))
      (node (ref "R16") (pin "1") (pinfunction "1_1") (pintype "passive"))
    )
    (net (code "30") (name "Net-(IC3-RS)") (class "Default")
      (node (ref "IC3") (pin "8") (pinfunction "RS_8") (pintype "bidirectional"))
      (node (ref "R18") (pin "1") (pinfunction "1_1") (pintype "passive"))
      (node (ref "R19") (pin "2") (pinfunction "2_2") (pintype "passive"))
    )
    (net (code "31") (name "Net-(IC4-ADJ+)") (class "Default")
      (node (ref "IC4") (pin "15") (pinfunction "ADJ+_15") (pintype "input"))
      (node (ref "R20") (pin "1") (pinfunction "1_1") (pintype "passive"))
      (node (ref "R21") (pin "2") (pinfunction "2_2") (pintype "passive"))
    )
    (net (code "32") (name "Net-(IC4-ADJ-)") (class "Default")
      (node (ref "IC4") (pin "4") (pinfunction "ADJ-_4") (pintype "input"))
      (node (ref "R22") (pin "1") (pinfunction "1_1") (pintype "passive"))
      (node (ref "R23") (pin "2") (pinfunction "2_2") (pintype "passive"))
    )
    (net (code "33") (name "Net-(IC4-BYP+)") (class "Default")
      (node (ref "C20") (pin "1") (pinfunction "1_1") (pintype "passive"))
      (node (ref "IC4") (pin "16") (pinfunction "BYP+_16") (pintype "bidirectional"))
    )
    (net (code "34") (name "Net-(IC4-BYP-)") (class "Default")
      (node (ref "C19") (pin "1") (pinfunction "1_1") (pintype "passive"))
      (node (ref "IC4") (pin "3") (pinfunction "BYP-_3") (pintype "bidirectional"))
    )
    (net (code "35") (name "Net-(IC4-C+)") (class "Default")
      (node (ref "C15") (pin "2") (pinfunction "2_2") (pintype "passive"))
      (node (ref "IC4") (pin "10") (pinfunction "C+_10") (pintype "bidirectional"))
    )
    (net (code "36") (name "Net-(IC4-C-)") (class "Default")
      (node (ref "C15") (pin "1") (pinfunction "1_1") (pintype "passive"))
      (node (ref "IC4") (pin "7") (pinfunction "C-_7") (pintype "bidirectional"))
    )
    (net (code "37") (name "Net-(IC4-VOUT)") (class "Default")
      (node (ref "C16") (pin "2") (pinfunction "2_2") (pintype "passive"))
      (node (ref "IC4") (pin "6") (pinfunction "VOUT_6") (pintype "output"))
    )
    (net (code "38") (name "Net-(J3-Pad1)") (class "Default")
      (node (ref "J3") (pin "1") (pinfunction "1_1") (pintype "passive"))
      (node (ref "R14") (pin "1") (pinfunction "1_1") (pintype "passive"))
    )
    (net (code "39") (name "Net-(Q1-D)") (class "Default")
      (node (ref "CON2") (pin "2") (pinfunction "2_2") (pintype "passive"))
      (node (ref "Q1") (pin "3") (pinfunction "D_3") (pintype "passive"))
    )
    (net (code "40") (name "Net-(Q2-D)") (class "Default")
      (node (ref "CON2") (pin "3") (pinfunction "3_3") (pintype "passive"))
      (node (ref "Q2") (pin "3") (pinfunction "D_3") (pintype "passive"))
    )
    (net (code "41") (name "Net-(U1-BOOT0)") (class "Default")
      (node (ref "R3") (pin "1") (pinfunction "1_1") (pintype "passive"))
      (node (ref "U1") (pin "31") (pinfunction "BOOT0_31") (pintype "input"))
    )
    (net (code "42") (name "Net-(U1-VDDA{slash}VREF+)") (class "Default")
      (node (ref "C2") (pin "1") (pinfunction "1_1") (pintype "passive"))
      (node (ref "R1") (pin "1") (pinfunction "1_1") (pintype "passive"))
      (node (ref "U1") (pin "5") (pinfunction "VDDA/VREF+_5") (pintype "power_in"))
    )
    (net (code "43") (name "R") (class "Default")
      (node (ref "IC3") (pin "4") (pinfunction "R_4") (pintype "bidirectional"))
      (node (ref "U1") (pin "21") (pinfunction "PA11_21") (pintype "bidirectional"))
    )
    (net (code "44") (name "RIGHT_STEP") (class "Default")
      (node (ref "Q1") (pin "1") (pinfunction "G_1") (pintype "passive"))
      (node (ref "R25") (pin "1") (pinfunction "1_1") (pintype "passive"))
      (node (ref "U1") (pin "30") (pinfunction "PB7_30") (pintype "bidirectional"))
    )
    (net (code "45") (name "RS") (class "Default")
      (node (ref "R18") (pin "2") (pinfunction "2_2") (pintype "passive"))
      (node (ref "U1") (pin "3") (pinfunction "PF1-OSC_OUT_3") (pintype "bidirectional"))
    )
    (net (code "46") (name "RX1") (class "Default")
      (node (ref "IC2") (pin "1") (pinfunction "RO_1") (pintype "bidirectional"))
      (node (ref "U1") (pin "20") (pinfunction "PA10_20") (pintype "bidirectional"))
    )
    (net (code "47") (name "RX2") (class "Default")
      (node (ref "J1") (pin "7") (pinfunction "7_7") (pintype "bidirectional"))
      (node (ref "U1") (pin "25") (pinfunction "PA15_25") (pintype "bidirectional"))
    )
    (net (code "48") (name "STM_12_INDIC") (class "Default")
      (node (ref "R7") (pin "2") (pinfunction "2_2") (pintype "passive"))
      (node (ref "R9") (pin "1") (pinfunction "1_1") (pintype "passive"))
      (node (ref "U1") (pin "7") (pinfunction "PA1_7") (pintype "bidirectional"))
    )
    (net (code "49") (name "SWDCLK") (class "Default")
      (node (ref "J1") (pin "4") (pinfunction "4_4") (pintype "bidirectional"))
      (node (ref "SWD1") (pin "4") (pinfunction "SWDCLK_4") (pintype "passive"))
      (node (ref "U1") (pin "24") (pinfunction "PA14_24") (pintype "bidirectional"))
    )
    (net (code "50") (name "SWDIO") (class "Default")
      (node (ref "J1") (pin "2") (pinfunction "2_2") (pintype "bidirectional"))
      (node (ref "SWD1") (pin "2") (pinfunction "SWDIO_2") (pintype "passive"))
      (node (ref "U1") (pin "23") (pinfunction "PA13_23") (pintype "bidirectional"))
    )
    (net (code "51") (name "SWO") (class "Default")
      (node (ref "J1") (pin "6") (pinfunction "6_6") (pintype "bidirectional"))
      (node (ref "SWD1") (pin "6") (pinfunction "SWO_6") (pintype "passive"))
      (node (ref "U1") (pin "26") (pinfunction "PB3_26") (pintype "bidirectional"))
    )
    (net (code "52") (name "TX1") (class "Default")
      (node (ref "IC2") (pin "4") (pinfunction "DI_4") (pintype "bidirectional"))
      (node (ref "U1") (pin "19") (pinfunction "PA9_19") (pintype "bidirectional"))
    )
    (net (code "53") (name "TX2") (class "Default")
      (node (ref "J1") (pin "8") (pinfunction "8_8") (pintype "bidirectional"))
      (node (ref "U1") (pin "8") (pinfunction "PA2_8") (pintype "bidirectional"))
    )
    (net (code "54") (name "unconnected-(H1-Pad1)") (class "Default")
      (node (ref "H1") (pin "1") (pinfunction "1_1") (pintype "bidirectional"))
    )
    (net (code "55") (name "unconnected-(H2-Pad1)") (class "Default")
      (node (ref "H2") (pin "1") (pinfunction "1_1") (pintype "bidirectional"))
    )
    (net (code "56") (name "unconnected-(H3-Pad1)") (class "Default")
      (node (ref "H3") (pin "1") (pinfunction "1_1") (pintype "bidirectional"))
    )
    (net (code "57") (name "unconnected-(H4-Pad1)") (class "Default")
      (node (ref "H4") (pin "1") (pinfunction "1_1") (pintype "bidirectional"))
    )
    (net (code "58") (name "unconnected-(H5-Pad1)") (class "Default")
      (node (ref "H5") (pin "1") (pinfunction "1_1") (pintype "bidirectional"))
    )
    (net (code "59") (name "unconnected-(IC3-VREF-Pad5)") (class "Default")
      (node (ref "IC3") (pin "5") (pinfunction "VREF_5") (pintype "bidirectional"))
    )
    (net (code "60") (name "unconnected-(IC4-EN+-Pad1)") (class "Default")
      (node (ref "IC4") (pin "1") (pinfunction "EN+_1") (pintype "input"))
    )
    (net (code "61") (name "unconnected-(IC4-EN--Pad13)") (class "Default")
      (node (ref "IC4") (pin "13") (pinfunction "EN-_13") (pintype "input"))
    )
    (net (code "62") (name "unconnected-(IC4-NC_1-Pad8)") (class "Default")
      (node (ref "IC4") (pin "8") (pinfunction "NC_1_8") (pintype "bidirectional"))
    )
    (net (code "63") (name "unconnected-(IC4-NC_2-Pad9)") (class "Default")
      (node (ref "IC4") (pin "9") (pinfunction "NC_2_9") (pintype "bidirectional"))
    )
    (net (code "64") (name "unconnected-(U1-PA3-Pad9)") (class "Default")
      (node (ref "U1") (pin "9") (pinfunction "PA3_9") (pintype "bidirectional"))
    )
    (net (code "65") (name "unconnected-(U1-PA6-Pad12)") (class "Default")
      (node (ref "U1") (pin "12") (pinfunction "PA6_12") (pintype "bidirectional"))
    )
    (net (code "66") (name "unconnected-(U1-PA7-Pad13)") (class "Default")
      (node (ref "U1") (pin "13") (pinfunction "PA7_13") (pintype "bidirectional"))
    )
    (net (code "67") (name "unconnected-(U1-PA8-Pad18)") (class "Default")
      (node (ref "U1") (pin "18") (pinfunction "PA8_18") (pintype "bidirectional"))
    )
    (net (code "68") (name "unconnected-(U1-PB1-Pad15)") (class "Default")
      (node (ref "U1") (pin "15") (pinfunction "PB1_15") (pintype "bidirectional"))
    )
    (net (code "69") (name "unconnected-(U1-PB4-Pad27)") (class "Default")
      (node (ref "U1") (pin "27") (pinfunction "PB4_27") (pintype "bidirectional"))
    )
    (net (code "70") (name "unconnected-(U1-PB5-Pad28)") (class "Default")
      (node (ref "U1") (pin "28") (pinfunction "PB5_28") (pintype "bidirectional"))
    )
    (net (code "71") (name "unconnected-(U1-PF0-OSC_IN-Pad2)") (class "Default")
      (node (ref "U1") (pin "2") (pinfunction "PF0-OSC_IN_2") (pintype "bidirectional"))
    )
  )
)
